# Pluvion_1_-_Rev_B.net
KiCad netlist of a schematic drawn in EAGLE
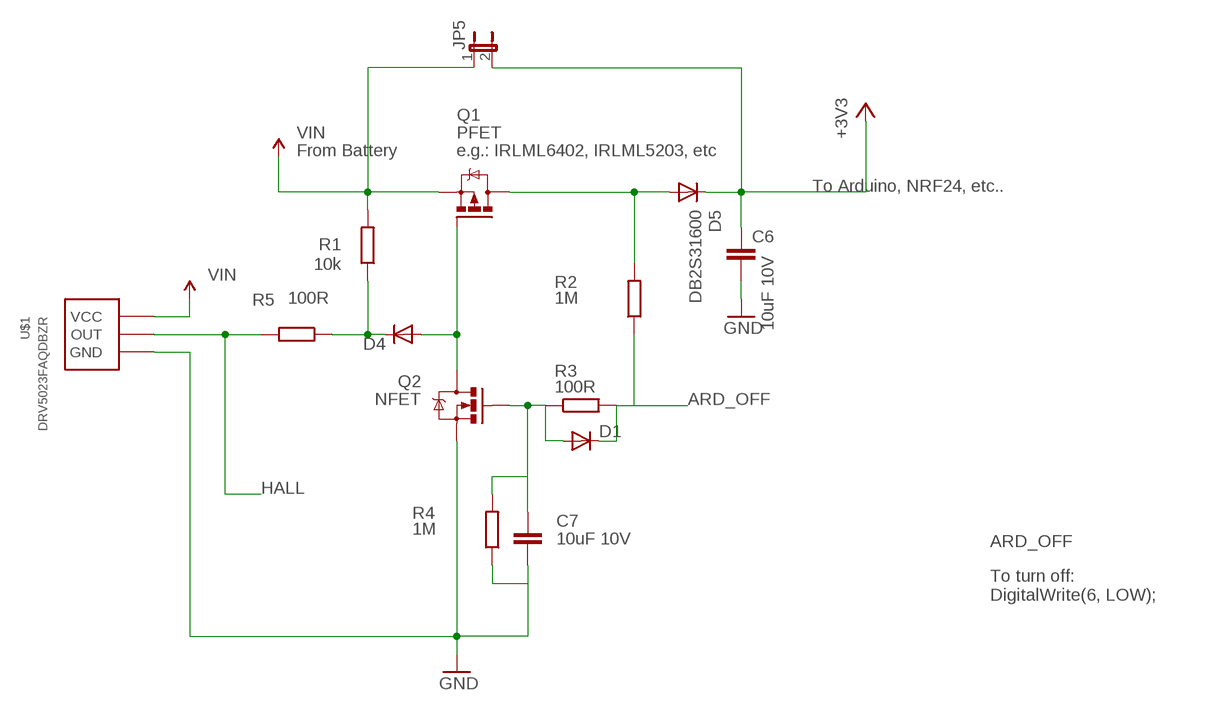
[diagram p0: schematic, sheet 1]
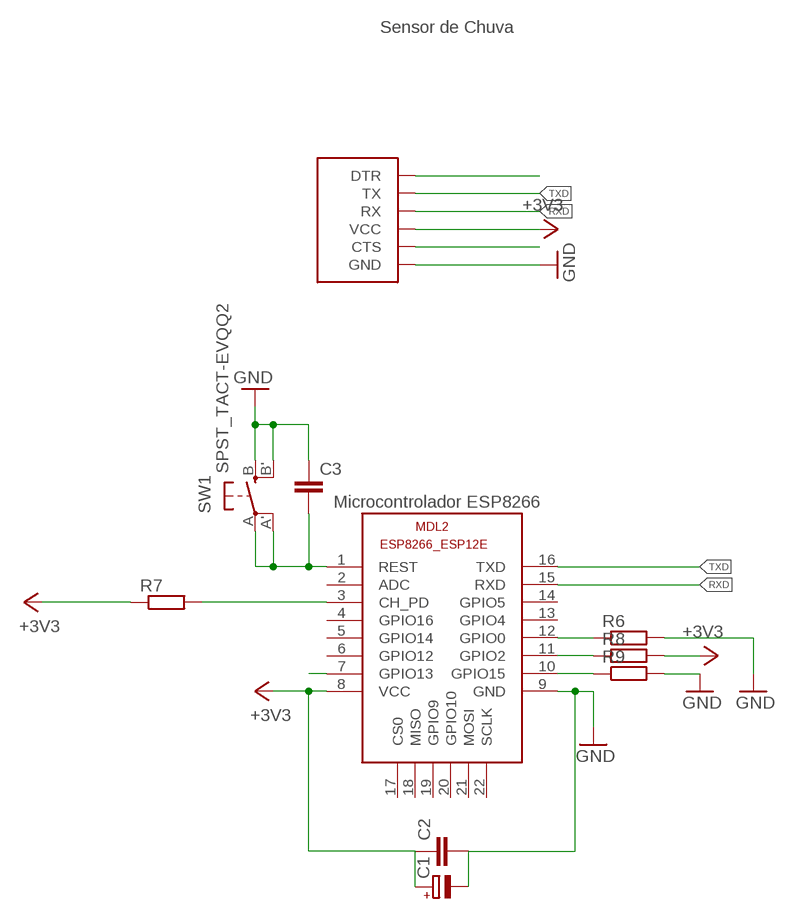
[diagram p1: schematic, sheet 3]

(export (version "E")
  (design (tool "Eeschema 10.0.6"))
  (components
    (comp (ref "C6")
      (value "10uF 10V")
      (footprint "eagle-import:C0805")
      (libsource (lib "eagle-import") (part "C-EUC0805"))
    )
    (comp (ref "C7")
      (value "10uF 10V")
      (footprint "eagle-import:C0805")
      (libsource (lib "eagle-import") (part "C-EUC0805"))
    )
    (comp (ref "D1")
      (value "DIODESMB")
      (footprint "eagle-import:SMB-DIODE")
      (libsource (lib "eagle-import") (part "DIODESMB"))
    )
    (comp (ref "D4")
      (value "DIODESMB")
      (footprint "eagle-import:SMB-DIODE")
      (libsource (lib "eagle-import") (part "DIODESMB"))
    )
    (comp (ref "D5")
      (value "DB2S31600")
      (footprint "eagle-import:SMB-DIODE")
      (libsource (lib "eagle-import") (part "DIODESMB"))
    )
    (comp (ref "JP5")
      (value "JUMPER-2PTH")
      (footprint "eagle-import:1X02")
      (libsource (lib "eagle-import") (part "JUMPER-2PTH"))
    )
    (comp (ref "Q1")
      (value "PFET")
      (footprint "eagle-import:MICRO3")
      (libsource (lib "eagle-import") (part "IRLML5203"))
    )
    (comp (ref "Q2")
      (value "NFET")
      (footprint "eagle-import:SOT23")
      (libsource (lib "eagle-import") (part "MOSFET-NCHANNELBSS123LT1G"))
    )
    (comp (ref "R1")
      (value "10k")
      (footprint "eagle-import:R0805")
      (libsource (lib "eagle-import") (part "R-EU_R0805"))
    )
    (comp (ref "R2")
      (value "1M")
      (footprint "eagle-import:R0805")
      (libsource (lib "eagle-import") (part "R-EU_R0805"))
    )
    (comp (ref "R3")
      (value "100R")
      (footprint "eagle-import:R0805")
      (libsource (lib "eagle-import") (part "R-EU_R0805"))
    )
    (comp (ref "R4")
      (value "1M")
      (footprint "eagle-import:R0805")
      (libsource (lib "eagle-import") (part "R-EU_R0805"))
    )
    (comp (ref "R5")
      (value "100R")
      (footprint "eagle-import:R0805")
      (libsource (lib "eagle-import") (part "R-EU_R0805"))
    )
    (comp (ref "U$1")
      (value "DRV5023FAQDBZR")
      (footprint "eagle-import:SOT23")
      (libsource (lib "eagle-import") (part "DRV5023FAQDBZR"))
    )
    (comp (ref "C1")
      (value "CPOL-EUC")
      (footprint "eagle-import:PANASONIC_C")
      (libsource (lib "eagle-import") (part "CPOL-EUC"))
    )
    (comp (ref "C2")
      (value "C-EUC0805")
      (footprint "eagle-import:C0805")
      (libsource (lib "eagle-import") (part "C-EUC0805"))
    )
    (comp (ref "C3")
      (value "C-EUC0805")
      (footprint "eagle-import:C0805")
      (libsource (lib "eagle-import") (part "C-EUC0805"))
    )
    (comp (ref "MDL2")
      (value "ESP8266-12EESP8266-ESP12E")
      (footprint "eagle-import:ESP8266-ESP12E")
      (libsource (lib "eagle-import") (part "ESP8266-12EESP8266-ESP12E"))
    )
    (comp (ref "R6")
      (value "R-EU_R0805")
      (footprint "eagle-import:R0805")
      (libsource (lib "eagle-import") (part "R-EU_R0805"))
    )
    (comp (ref "R7")
      (value "R-EU_R0805")
      (footprint "eagle-import:R0805")
      (libsource (lib "eagle-import") (part "R-EU_R0805"))
    )
    (comp (ref "R8")
      (value "R-EU_R0805")
      (footprint "eagle-import:R0805")
      (libsource (lib "eagle-import") (part "R-EU_R0805"))
    )
    (comp (ref "R9")
      (value "R-EU_R0805")
      (footprint "eagle-import:R0805")
      (libsource (lib "eagle-import") (part "R-EU_R0805"))
    )
    (comp (ref "SW1")
      (value "SPST_TACT-EVQQ2")
      (footprint "eagle-import:EVQ-Q2")
      (libsource (lib "eagle-import") (part "SPST_TACT-EVQQ2"))
    )
    (comp (ref "U$2")
      (value "FTDI_HEADERSMD")
      (footprint "eagle-import:FTDI_HEADER_SMD")
      (libsource (lib "eagle-import") (part "FTDI_HEADERSMD"))
    )
  )
  (nets
    (net (code "1") (name "+3V3") (class "Default")
      (node (ref "C1") (pin "+") (pinfunction "+_+") (pintype "passive"))
      (node (ref "C2") (pin "1") (pinfunction "1_1") (pintype "passive"))
      (node (ref "C6") (pin "1") (pinfunction "1_1") (pintype "passive"))
      (node (ref "D5") (pin "C") (pinfunction "C_C") (pintype "passive"))
      (node (ref "JP5") (pin "2") (pinfunction "2_2") (pintype "passive"))
      (node (ref "MDL2") (pin "8") (pinfunction "VCC_8") (pintype "bidirectional"))
      (node (ref "R7") (pin "1") (pinfunction "1_1") (pintype "passive"))
      (node (ref "R8") (pin "2") (pinfunction "2_2") (pintype "passive"))
      (node (ref "U$2") (pin "VCC") (pinfunction "VCC_VCC") (pintype "bidirectional"))
    )
    (net (code "2") (name "ARD_OFF") (class "Default")
      (node (ref "D1") (pin "C") (pinfunction "C_C") (pintype "passive"))
      (node (ref "MDL2") (pin "7") (pinfunction "GPIO13_7") (pintype "bidirectional"))
      (node (ref "R2") (pin "1") (pinfunction "1_1") (pintype "passive"))
      (node (ref "R3") (pin "2") (pinfunction "2_2") (pintype "passive"))
    )
    (net (code "3") (name "GND") (class "Default")
      (node (ref "C1") (pin "-") (pinfunction "-_-") (pintype "passive"))
      (node (ref "C2") (pin "2") (pinfunction "2_2") (pintype "passive"))
      (node (ref "C3") (pin "1") (pinfunction "1_1") (pintype "passive"))
      (node (ref "C6") (pin "2") (pinfunction "2_2") (pintype "passive"))
      (node (ref "C7") (pin "2") (pinfunction "2_2") (pintype "passive"))
      (node (ref "MDL2") (pin "9") (pinfunction "GND_9") (pintype "bidirectional"))
      (node (ref "Q2") (pin "2") (pinfunction "S_2") (pintype "passive"))
      (node (ref "R4") (pin "1") (pinfunction "1_1") (pintype "passive"))
      (node (ref "R6") (pin "2") (pinfunction "2_2") (pintype "passive"))
      (node (ref "R9") (pin "2") (pinfunction "2_2") (pintype "passive"))
      (node (ref "SW1") (pin "B") (pinfunction "S_B") (pintype "passive"))
      (node (ref "SW1") (pin "B'") (pinfunction "S1_B'") (pintype "passive"))
      (node (ref "U$1") (pin "3") (pinfunction "GND_3") (pintype "bidirectional"))
      (node (ref "U$2") (pin "GND") (pinfunction "GND_GND") (pintype "bidirectional"))
    )
    (net (code "4") (name "HALL") (class "Default")
      (node (ref "R5") (pin "2") (pinfunction "2_2") (pintype "passive"))
      (node (ref "U$1") (pin "2") (pinfunction "OUT_2") (pintype "bidirectional"))
    )
    (net (code "5") (name "Net-(D4-PadC)") (class "Default")
      (node (ref "D4") (pin "C") (pinfunction "C_C") (pintype "passive"))
      (node (ref "R1") (pin "1") (pinfunction "1_1") (pintype "passive"))
      (node (ref "R5") (pin "1") (pinfunction "1_1") (pintype "passive"))
    )
    (net (code "6") (name "Net-(MDL2-CH_PD)") (class "Default")
      (node (ref "MDL2") (pin "3") (pinfunction "CH_PD_3") (pintype "bidirectional"))
      (node (ref "R7") (pin "2") (pinfunction "2_2") (pintype "passive"))
    )
    (net (code "7") (name "Net-(MDL2-GPIO0)") (class "Default")
      (node (ref "MDL2") (pin "12") (pinfunction "GPIO0_12") (pintype "bidirectional"))
      (node (ref "R6") (pin "1") (pinfunction "1_1") (pintype "passive"))
    )
    (net (code "8") (name "Net-(MDL2-GPIO2)") (class "Default")
      (node (ref "MDL2") (pin "11") (pinfunction "GPIO2_11") (pintype "bidirectional"))
      (node (ref "R8") (pin "1") (pinfunction "1_1") (pintype "passive"))
    )
    (net (code "9") (name "Net-(MDL2-GPIO15)") (class "Default")
      (node (ref "MDL2") (pin "10") (pinfunction "GPIO15_10") (pintype "bidirectional"))
      (node (ref "R9") (pin "1") (pinfunction "1_1") (pintype "passive"))
    )
    (net (code "10") (name "Net-(MDL2-REST)") (class "Default")
      (node (ref "C3") (pin "2") (pinfunction "2_2") (pintype "passive"))
      (node (ref "MDL2") (pin "1") (pinfunction "REST_1") (pintype "bidirectional"))
      (node (ref "SW1") (pin "A") (pinfunction "P_A") (pintype "passive"))
      (node (ref "SW1") (pin "A'") (pinfunction "P1_A'") (pintype "passive"))
    )
    (net (code "11") (name "Net-(Q1-D)") (class "Default")
      (node (ref "D5") (pin "A") (pinfunction "A_A") (pintype "passive"))
      (node (ref "Q1") (pin "3") (pinfunction "D_3") (pintype "passive"))
      (node (ref "R2") (pin "2") (pinfunction "2_2") (pintype "passive"))
    )
    (net (code "12") (name "Net-(Q1-G)") (class "Default")
      (node (ref "D4") (pin "A") (pinfunction "A_A") (pintype "passive"))
      (node (ref "Q1") (pin "1") (pinfunction "G_1") (pintype "passive"))
      (node (ref "Q2") (pin "3") (pinfunction "D_3") (pintype "passive"))
    )
    (net (code "13") (name "Net-(Q2-G)") (class "Default")
      (node (ref "C7") (pin "1") (pinfunction "1_1") (pintype "passive"))
      (node (ref "D1") (pin "A") (pinfunction "A_A") (pintype "passive"))
      (node (ref "Q2") (pin "1") (pinfunction "G_1") (pintype "passive"))
      (node (ref "R3") (pin "1") (pinfunction "1_1") (pintype "passive"))
      (node (ref "R4") (pin "2") (pinfunction "2_2") (pintype "passive"))
    )
    (net (code "14") (name "RXD") (class "Default")
      (node (ref "MDL2") (pin "15") (pinfunction "RXD_15") (pintype "bidirectional"))
      (node (ref "U$2") (pin "RX") (pinfunction "RX_RX") (pintype "bidirectional"))
    )
    (net (code "15") (name "TXD") (class "Default")
      (node (ref "MDL2") (pin "16") (pinfunction "TXD_16") (pintype "bidirectional"))
      (node (ref "U$2") (pin "TX") (pinfunction "TX_TX") (pintype "bidirectional"))
    )
    (net (code "16") (name "VIN") (class "Default")
      (node (ref "JP5") (pin "1") (pinfunction "1_1") (pintype "passive"))
      (node (ref "Q1") (pin "2") (pinfunction "S_2") (pintype "passive"))
      (node (ref "R1") (pin "2") (pinfunction "2_2") (pintype "passive"))
      (node (ref "U$1") (pin "1") (pinfunction "VCC_1") (pintype "bidirectional"))
    )
    (net (code "17") (name "unconnected-(MDL2-ADC-Pad2)") (class "Default")
      (node (ref "MDL2") (pin "2") (pinfunction "ADC_2") (pintype "bidirectional"))
    )
    (net (code "18") (name "unconnected-(MDL2-CS0-Pad17)") (class "Default")
      (node (ref "MDL2") (pin "17") (pinfunction "CS0_17") (pintype "bidirectional"))
    )
    (net (code "19") (name "unconnected-(MDL2-GPIO4-Pad13)") (class "Default")
      (node (ref "MDL2") (pin "13") (pinfunction "GPIO4_13") (pintype "bidirectional"))
    )
    (net (code "20") (name "unconnected-(MDL2-GPIO5-Pad14)") (class "Default")
      (node (ref "MDL2") (pin "14") (pinfunction "GPIO5_14") (pintype "bidirectional"))
    )
    (net (code "21") (name "unconnected-(MDL2-GPIO9-Pad19)") (class "Default")
      (node (ref "MDL2") (pin "19") (pinfunction "GPIO9_19") (pintype "bidirectional"))
    )
    (net (code "22") (name "unconnected-(MDL2-GPIO10-Pad20)") (class "Default")
      (node (ref "MDL2") (pin "20") (pinfunction "GPIO10_20") (pintype "bidirectional"))
    )
    (net (code "23") (name "unconnected-(MDL2-GPIO12-Pad6)") (class "Default")
      (node (ref "MDL2") (pin "6") (pinfunction "GPIO12_6") (pintype "bidirectional"))
    )
    (net (code "24") (name "unconnected-(MDL2-GPIO14-Pad5)") (class "Default")
      (node (ref "MDL2") (pin "5") (pinfunction "GPIO14_5") (pintype "bidirectional"))
    )
    (net (code "25") (name "unconnected-(MDL2-GPIO16-Pad4)") (class "Default")
      (node (ref "MDL2") (pin "4") (pinfunction "GPIO16_4") (pintype "bidirectional"))
    )
    (net (code "26") (name "unconnected-(MDL2-MISO-Pad18)") (class "Default")
      (node (ref "MDL2") (pin "18") (pinfunction "MISO_18") (pintype "bidirectional"))
    )
    (net (code "27") (name "unconnected-(MDL2-MOSI-Pad21)") (class "Default")
      (node (ref "MDL2") (pin "21") (pinfunction "MOSI_21") (pintype "bidirectional"))
    )
    (net (code "28") (name "unconnected-(MDL2-SCLK-Pad22)") (class "Default")
      (node (ref "MDL2") (pin "22") (pinfunction "SCLK_22") (pintype "bidirectional"))
    )
    (net (code "29") (name "unconnected-(U$2-PadCTS)") (class "Default")
      (node (ref "U$2") (pin "CTS") (pinfunction "CTS_CTS") (pintype "bidirectional"))
    )
    (net (code "30") (name "unconnected-(U$2-PadDTR)") (class "Default")
      (node (ref "U$2") (pin "DTR") (pinfunction "DTR_DTR") (pintype "bidirectional"))
    )
  )
)
